# plug-v23-change-C-at-power-supply.net
KiCad netlist of a schematic drawn in EAGLE
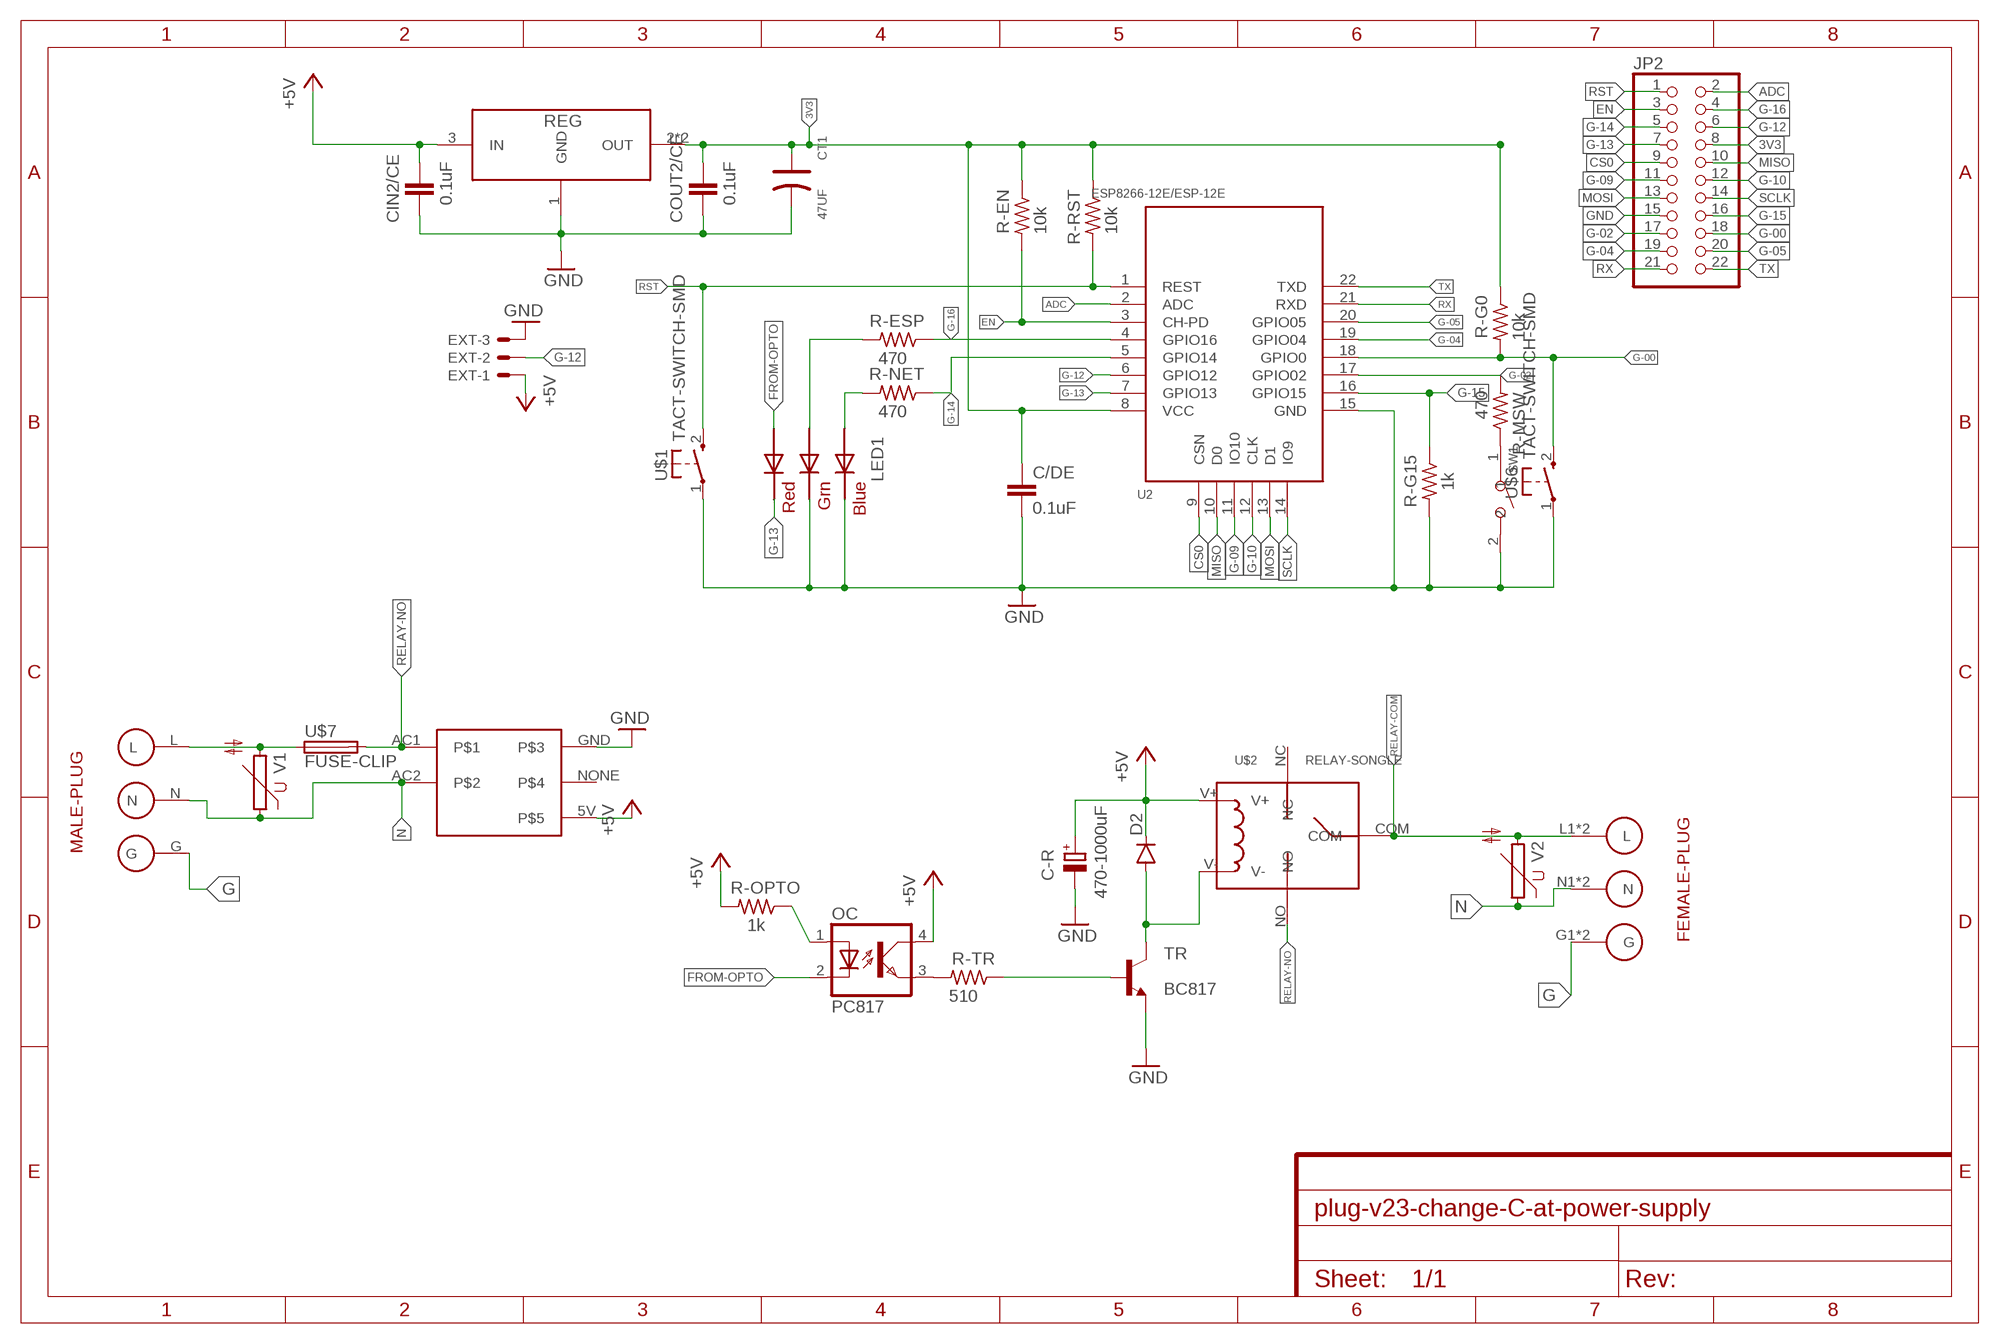
[diagram p0: schematic, sheet 1]

(export (version "E")
  (design (tool "Eeschema 10.0.6"))
  (components
    (comp (ref "C-R")
      (value "470-1000uF")
      (footprint "eagle-import:E3,5-8")
      (libsource (lib "eagle-import") (part "CPOL-EUE3.5-8"))
    )
    (comp (ref "C/DE")
      (value "0.1uF")
      (footprint "eagle-import:C0805")
      (libsource (lib "eagle-import") (part "C-EUC0805"))
    )
    (comp (ref "CIN2/CE")
      (value "0.1uF")
      (footprint "eagle-import:C0805K")
      (libsource (lib "eagle-import") (part "C-EUC0805K"))
    )
    (comp (ref "COUT2/CE")
      (value "0.1uF")
      (footprint "eagle-import:C0805K")
      (libsource (lib "eagle-import") (part "C-EUC0805K"))
    )
    (comp (ref "CT1")
      (value "47UF")
      (footprint "eagle-import:ELECTRO-SMD-C-6MM")
      (fields (field (name "MPN") "CS1E470M-CRE54"))
      (libsource (lib "eagle-import") (part "ALUMINUM-SMD-47UF-25V(D6.3-H5.3MM)"))
    )
    (comp (ref "D2")
      (value "DIODESOD123")
      (footprint "eagle-import:SOD-123")
      (libsource (lib "eagle-import") (part "DIODESOD123"))
    )
    (comp (ref "EXT")
      (value "53048-03")
      (footprint "eagle-import:53048-03")
      (fields (field (name "MF") "WALDOM/MOLEX") (field (name "MPN") "53048-0310"))
      (libsource (lib "eagle-import") (part "53?-03048"))
    )
    (comp (ref "JP2")
      (value "PINHD-2X11")
      (footprint "eagle-import:2X11")
      (libsource (lib "eagle-import") (part "PINHD-2X11"))
    )
    (comp (ref "LED1")
      (value "RGBLED5050")
      (footprint "eagle-import:RGBLED5050")
      (libsource (lib "eagle-import") (part "RGBLED5050"))
    )
    (comp (ref "OC")
      (value "PC817")
      (footprint "eagle-import:DIL04")
      (fields (field (name "MPN") "PC817X4J000F"))
      (libsource (lib "eagle-import") (part "PC817"))
    )
    (comp (ref "R-EN")
      (value "10k")
      (footprint "eagle-import:M0805")
      (libsource (lib "eagle-import") (part "R-US_M0805"))
    )
    (comp (ref "R-ESP")
      (value "470")
      (footprint "eagle-import:M0805")
      (libsource (lib "eagle-import") (part "R-US_M0805"))
    )
    (comp (ref "R-G0")
      (value "10k")
      (footprint "eagle-import:M0805")
      (libsource (lib "eagle-import") (part "R-US_M0805"))
    )
    (comp (ref "R-G15")
      (value "1k")
      (footprint "eagle-import:M0805")
      (libsource (lib "eagle-import") (part "R-US_M0805"))
    )
    (comp (ref "R-MSW")
      (value "470")
      (footprint "eagle-import:M0805")
      (libsource (lib "eagle-import") (part "R-US_M0805"))
    )
    (comp (ref "R-NET")
      (value "470")
      (footprint "eagle-import:M0805")
      (libsource (lib "eagle-import") (part "R-US_M0805"))
    )
    (comp (ref "R-OPTO")
      (value "1k")
      (footprint "eagle-import:M0805")
      (libsource (lib "eagle-import") (part "R-US_M0805"))
    )
    (comp (ref "R-RST")
      (value "10k")
      (footprint "eagle-import:M0805")
      (libsource (lib "eagle-import") (part "R-US_M0805"))
    )
    (comp (ref "R-TR")
      (value "510")
      (footprint "eagle-import:M0805")
      (libsource (lib "eagle-import") (part "R-US_M0805"))
    )
    (comp (ref "REG")
      (value "AMS1117-3.3")
      (footprint "eagle-import:SOT-223")
      (libsource (lib "eagle-import") (part "AMS1117-3.3"))
    )
    (comp (ref "SW1")
      (value "DIP-BUTTON(2P-6.0X3.0X4.3MM)-TS-1101F")
      (footprint "eagle-import:SW2-5.0-6.0X3.0X4.3MM")
      (libsource (lib "eagle-import") (part "DIP-BUTTON(2P-6.0X3.0X4.3MM)-TS-1101F"))
    )
    (comp (ref "TR")
      (value "BC817")
      (footprint "eagle-import:SOT23-BEC")
      (libsource (lib "eagle-import") (part "BC817SMD-16"))
    )
    (comp (ref "U$1")
      (value "TACT-SWITCH-SMD")
      (footprint "eagle-import:TACT-SWITCH-SMD")
      (libsource (lib "eagle-import") (part "TACT-SWITCH-SMD"))
    )
    (comp (ref "U$2")
      (value "RELAY-SONGLE")
      (footprint "eagle-import:RELAY-SONGLE")
      (libsource (lib "eagle-import") (part "RELAY-SONGLE"))
    )
    (comp (ref "U$3")
      (value "MALE-PLUG")
      (footprint "eagle-import:MALE-PLUG")
      (libsource (lib "eagle-import") (part "MALE-PLUG"))
    )
    (comp (ref "U$4")
      (value "POWERSUPPLY-5V-700MA")
      (footprint "eagle-import:POWERSUPPLY-5V-700MA")
      (libsource (lib "eagle-import") (part "POWERSUPPLY-5V-700MA"))
    )
    (comp (ref "U$5")
      (value "FEMALE-PLUG")
      (footprint "eagle-import:FEMALE-PLUG")
      (libsource (lib "eagle-import") (part "FEMALE-PLUG"))
    )
    (comp (ref "U$6")
      (value "TACT-SWITCH-SMD")
      (footprint "eagle-import:TACT-SWITCH-SMD")
      (libsource (lib "eagle-import") (part "TACT-SWITCH-SMD"))
    )
    (comp (ref "U$7")
      (value "FUSE-CLIP")
      (footprint "eagle-import:FUSE-CLIP")
      (libsource (lib "eagle-import") (part "FUSE-CLIP"))
    )
    (comp (ref "U2")
      (value "ESP8266-12E/ESP-12E")
      (footprint "eagle-import:LGA22-2.0-24X16MM")
      (libsource (lib "eagle-import") (part "MOUDLE-WIFI-ESP8266-12E/ESP-12E(22P-24X16MM)"))
    )
    (comp (ref "V1")
      (value "S14K11")
      (footprint "eagle-import:S14K11")
      (libsource (lib "eagle-import") (part "S14K11"))
    )
    (comp (ref "V2")
      (value "S14K11")
      (footprint "eagle-import:S14K11")
      (libsource (lib "eagle-import") (part "S14K11"))
    )
  )
  (nets
    (net (code "1") (name "+5V") (class "Default")
      (node (ref "C-R") (pin "+") (pinfunction "+_+") (pintype "passive"))
      (node (ref "CIN2/CE") (pin "1") (pinfunction "1_1") (pintype "passive"))
      (node (ref "D2") (pin "C") (pinfunction "C_C") (pintype "passive"))
      (node (ref "EXT") (pin "1") (pinfunction "S_1") (pintype "passive"))
      (node (ref "OC") (pin "4") (pinfunction "COL_4") (pintype "passive"))
      (node (ref "R-OPTO") (pin "2") (pinfunction "2_2") (pintype "passive"))
      (node (ref "REG") (pin "3") (pinfunction "IN_3") (pintype "input"))
      (node (ref "U$2") (pin "V+") (pinfunction "V+_V+") (pintype "bidirectional"))
      (node (ref "U$4") (pin "5V") (pinfunction "P$5_5V") (pintype "bidirectional"))
    )
    (net (code "2") (name "3V3") (class "Default")
      (node (ref "C/DE") (pin "1") (pinfunction "1_1") (pintype "passive"))
      (node (ref "COUT2/CE") (pin "1") (pinfunction "1_1") (pintype "passive"))
      (node (ref "CT1") (pin "+") (pinfunction "+_+") (pintype "passive"))
      (node (ref "JP2") (pin "8") (pinfunction "8_8") (pintype "passive"))
      (node (ref "R-EN") (pin "1") (pinfunction "1_1") (pintype "passive"))
      (node (ref "R-G0") (pin "1") (pinfunction "1_1") (pintype "passive"))
      (node (ref "R-RST") (pin "1") (pinfunction "1_1") (pintype "passive"))
      (node (ref "REG") (pin "2") (pinfunction "OUT_2") (pintype "output"))
      (node (ref "REG") (pin "4") (pinfunction "OUT_4") (pintype "output"))
      (node (ref "U2") (pin "8") (pinfunction "VCC_8") (pintype "bidirectional"))
    )
    (net (code "3") (name "ADC") (class "Default")
      (node (ref "JP2") (pin "2") (pinfunction "2_2") (pintype "passive"))
      (node (ref "U2") (pin "2") (pinfunction "ADC_2") (pintype "bidirectional"))
    )
    (net (code "4") (name "CS0") (class "Default")
      (node (ref "JP2") (pin "9") (pinfunction "9_9") (pintype "passive"))
      (node (ref "U2") (pin "9") (pinfunction "CSN_9") (pintype "bidirectional"))
    )
    (net (code "5") (name "EN") (class "Default")
      (node (ref "JP2") (pin "3") (pinfunction "3_3") (pintype "passive"))
      (node (ref "R-EN") (pin "2") (pinfunction "2_2") (pintype "passive"))
      (node (ref "U2") (pin "3") (pinfunction "CH-PD_3") (pintype "bidirectional"))
    )
    (net (code "6") (name "FROM-OPTO") (class "Default")
      (node (ref "LED1") (pin "2") (pinfunction "RED_A_2") (pintype "bidirectional"))
      (node (ref "OC") (pin "2") (pinfunction "C_2") (pintype "passive"))
    )
    (net (code "7") (name "G") (class "Default")
      (node (ref "U$3") (pin "G") (pinfunction "G_G") (pintype "bidirectional"))
      (node (ref "U$5") (pin "G1") (pinfunction "G_G1") (pintype "bidirectional"))
      (node (ref "U$5") (pin "G2") (pinfunction "G_G2") (pintype "bidirectional"))
    )
    (net (code "8") (name "G-00") (class "Default")
      (node (ref "JP2") (pin "18") (pinfunction "18_18") (pintype "passive"))
      (node (ref "R-G0") (pin "2") (pinfunction "2_2") (pintype "passive"))
      (node (ref "U$6") (pin "2") (pinfunction "S_2") (pintype "passive"))
      (node (ref "U2") (pin "18") (pinfunction "GPIO0_18") (pintype "bidirectional"))
    )
    (net (code "9") (name "G-02") (class "Default")
      (node (ref "JP2") (pin "17") (pinfunction "17_17") (pintype "passive"))
      (node (ref "R-MSW") (pin "2") (pinfunction "2_2") (pintype "passive"))
      (node (ref "U2") (pin "17") (pinfunction "GPIO02_17") (pintype "bidirectional"))
    )
    (net (code "10") (name "G-04") (class "Default")
      (node (ref "JP2") (pin "19") (pinfunction "19_19") (pintype "passive"))
      (node (ref "U2") (pin "19") (pinfunction "GPIO04_19") (pintype "bidirectional"))
    )
    (net (code "11") (name "G-05") (class "Default")
      (node (ref "JP2") (pin "20") (pinfunction "20_20") (pintype "passive"))
      (node (ref "U2") (pin "20") (pinfunction "GPIO05_20") (pintype "bidirectional"))
    )
    (net (code "12") (name "G-09") (class "Default")
      (node (ref "JP2") (pin "11") (pinfunction "11_11") (pintype "passive"))
      (node (ref "U2") (pin "11") (pinfunction "IO10_11") (pintype "bidirectional"))
    )
    (net (code "13") (name "G-10") (class "Default")
      (node (ref "JP2") (pin "12") (pinfunction "12_12") (pintype "passive"))
      (node (ref "U2") (pin "12") (pinfunction "CLK_12") (pintype "bidirectional"))
    )
    (net (code "14") (name "G-12") (class "Default")
      (node (ref "EXT") (pin "2") (pinfunction "S_2") (pintype "passive"))
      (node (ref "JP2") (pin "6") (pinfunction "6_6") (pintype "passive"))
      (node (ref "U2") (pin "6") (pinfunction "GPIO12_6") (pintype "bidirectional"))
    )
    (net (code "15") (name "G-13") (class "Default")
      (node (ref "JP2") (pin "7") (pinfunction "7_7") (pintype "passive"))
      (node (ref "LED1") (pin "5") (pinfunction "RED_C_5") (pintype "bidirectional"))
      (node (ref "U2") (pin "7") (pinfunction "GPIO13_7") (pintype "bidirectional"))
    )
    (net (code "16") (name "G-14") (class "Default")
      (node (ref "JP2") (pin "5") (pinfunction "5_5") (pintype "passive"))
      (node (ref "R-NET") (pin "1") (pinfunction "1_1") (pintype "passive"))
      (node (ref "U2") (pin "5") (pinfunction "GPIO14_5") (pintype "bidirectional"))
    )
    (net (code "17") (name "G-15") (class "Default")
      (node (ref "JP2") (pin "16") (pinfunction "16_16") (pintype "passive"))
      (node (ref "R-G15") (pin "1") (pinfunction "1_1") (pintype "passive"))
      (node (ref "U2") (pin "16") (pinfunction "GPIO15_16") (pintype "bidirectional"))
    )
    (net (code "18") (name "G-16") (class "Default")
      (node (ref "JP2") (pin "4") (pinfunction "4_4") (pintype "passive"))
      (node (ref "R-ESP") (pin "1") (pinfunction "1_1") (pintype "passive"))
      (node (ref "U2") (pin "4") (pinfunction "GPIO16_4") (pintype "bidirectional"))
    )
    (net (code "19") (name "GND") (class "Default")
      (node (ref "C-R") (pin "-") (pinfunction "-_-") (pintype "passive"))
      (node (ref "C/DE") (pin "2") (pinfunction "2_2") (pintype "passive"))
      (node (ref "CIN2/CE") (pin "2") (pinfunction "2_2") (pintype "passive"))
      (node (ref "COUT2/CE") (pin "2") (pinfunction "2_2") (pintype "passive"))
      (node (ref "CT1") (pin "-") (pinfunction "-_-") (pintype "passive"))
      (node (ref "EXT") (pin "3") (pinfunction "S_3") (pintype "passive"))
      (node (ref "JP2") (pin "15") (pinfunction "15_15") (pintype "passive"))
      (node (ref "LED1") (pin "4") (pinfunction "BLUE_C_4") (pintype "bidirectional"))
      (node (ref "LED1") (pin "6") (pinfunction "GREEN_C_6") (pintype "bidirectional"))
      (node (ref "R-G15") (pin "2") (pinfunction "2_2") (pintype "passive"))
      (node (ref "REG") (pin "1") (pinfunction "GND_1") (pintype "passive"))
      (node (ref "SW1") (pin "2") (pinfunction "2_2") (pintype "bidirectional"))
      (node (ref "TR") (pin "E") (pinfunction "E_E") (pintype "passive"))
      (node (ref "U$1") (pin "1") (pinfunction "P_1") (pintype "passive"))
      (node (ref "U$4") (pin "GND") (pinfunction "P$3_GND") (pintype "bidirectional"))
      (node (ref "U$6") (pin "1") (pinfunction "P_1") (pintype "passive"))
      (node (ref "U2") (pin "15") (pinfunction "GND_15") (pintype "bidirectional"))
    )
    (net (code "20") (name "MISO") (class "Default")
      (node (ref "JP2") (pin "10") (pinfunction "10_10") (pintype "passive"))
      (node (ref "U2") (pin "10") (pinfunction "D0_10") (pintype "bidirectional"))
    )
    (net (code "21") (name "MOSI") (class "Default")
      (node (ref "JP2") (pin "13") (pinfunction "13_13") (pintype "passive"))
      (node (ref "U2") (pin "13") (pinfunction "D1_13") (pintype "bidirectional"))
    )
    (net (code "22") (name "N") (class "Default")
      (node (ref "U$3") (pin "N") (pinfunction "N_N") (pintype "bidirectional"))
      (node (ref "U$4") (pin "AC2") (pinfunction "P$2_AC2") (pintype "bidirectional"))
      (node (ref "U$5") (pin "N1") (pinfunction "N_N1") (pintype "bidirectional"))
      (node (ref "U$5") (pin "N2") (pinfunction "N_N2") (pintype "bidirectional"))
      (node (ref "V1") (pin "1") (pinfunction "1_1") (pintype "passive"))
      (node (ref "V2") (pin "1") (pinfunction "1_1") (pintype "passive"))
    )
    (net (code "23") (name "Net-(D2-PadA)") (class "Default")
      (node (ref "D2") (pin "A") (pinfunction "A_A") (pintype "passive"))
      (node (ref "TR") (pin "C") (pinfunction "C_C") (pintype "passive"))
      (node (ref "U$2") (pin "V-") (pinfunction "V-_V-") (pintype "bidirectional"))
    )
    (net (code "24") (name "Net-(LED1-BLUE_A)") (class "Default")
      (node (ref "LED1") (pin "3") (pinfunction "BLUE_A_3") (pintype "bidirectional"))
      (node (ref "R-NET") (pin "2") (pinfunction "2_2") (pintype "passive"))
    )
    (net (code "25") (name "Net-(LED1-GREEN_A)") (class "Default")
      (node (ref "LED1") (pin "1") (pinfunction "GREEN_A_1") (pintype "bidirectional"))
      (node (ref "R-ESP") (pin "2") (pinfunction "2_2") (pintype "passive"))
    )
    (net (code "26") (name "Net-(OC-A)") (class "Default")
      (node (ref "OC") (pin "1") (pinfunction "A_1") (pintype "passive"))
      (node (ref "R-OPTO") (pin "1") (pinfunction "1_1") (pintype "passive"))
    )
    (net (code "27") (name "Net-(OC-EMIT)") (class "Default")
      (node (ref "OC") (pin "3") (pinfunction "EMIT_3") (pintype "passive"))
      (node (ref "R-TR") (pin "2") (pinfunction "2_2") (pintype "passive"))
    )
    (net (code "28") (name "Net-(R-MSW-Pad1)") (class "Default")
      (node (ref "R-MSW") (pin "1") (pinfunction "1_1") (pintype "passive"))
      (node (ref "SW1") (pin "1") (pinfunction "1_1") (pintype "bidirectional"))
    )
    (net (code "29") (name "Net-(R-TR-Pad1)") (class "Default")
      (node (ref "R-TR") (pin "1") (pinfunction "1_1") (pintype "passive"))
      (node (ref "TR") (pin "B") (pinfunction "B_B") (pintype "passive"))
    )
    (net (code "30") (name "Net-(U$3-PadL)") (class "Default")
      (node (ref "U$3") (pin "L") (pinfunction "L_L") (pintype "bidirectional"))
      (node (ref "U$7") (pin "3") (pinfunction "1_3") (pintype "passive"))
      (node (ref "U$7") (pin "4") (pinfunction "1_4") (pintype "passive"))
      (node (ref "V1") (pin "2") (pinfunction "2_2") (pintype "passive"))
    )
    (net (code "31") (name "RELAY-COM") (class "Default")
      (node (ref "U$2") (pin "COM") (pinfunction "COM_COM") (pintype "bidirectional"))
      (node (ref "U$5") (pin "L1") (pinfunction "L_L1") (pintype "bidirectional"))
      (node (ref "U$5") (pin "L2") (pinfunction "L_L2") (pintype "bidirectional"))
      (node (ref "V2") (pin "2") (pinfunction "2_2") (pintype "passive"))
    )
    (net (code "32") (name "RELAY-NO") (class "Default")
      (node (ref "U$2") (pin "NO") (pinfunction "NO_NO") (pintype "bidirectional"))
      (node (ref "U$4") (pin "AC1") (pinfunction "P$1_AC1") (pintype "bidirectional"))
      (node (ref "U$7") (pin "5") (pinfunction "2_5") (pintype "passive"))
      (node (ref "U$7") (pin "6") (pinfunction "2_6") (pintype "passive"))
    )
    (net (code "33") (name "RST") (class "Default")
      (node (ref "JP2") (pin "1") (pinfunction "1_1") (pintype "passive"))
      (node (ref "R-RST") (pin "2") (pinfunction "2_2") (pintype "passive"))
      (node (ref "U$1") (pin "2") (pinfunction "S_2") (pintype "passive"))
      (node (ref "U2") (pin "1") (pinfunction "REST_1") (pintype "bidirectional"))
    )
    (net (code "34") (name "RX") (class "Default")
      (node (ref "JP2") (pin "21") (pinfunction "21_21") (pintype "passive"))
      (node (ref "U2") (pin "21") (pinfunction "RXD_21") (pintype "bidirectional"))
    )
    (net (code "35") (name "SCLK") (class "Default")
      (node (ref "JP2") (pin "14") (pinfunction "14_14") (pintype "passive"))
      (node (ref "U2") (pin "14") (pinfunction "IO9_14") (pintype "bidirectional"))
    )
    (net (code "36") (name "TX") (class "Default")
      (node (ref "JP2") (pin "22") (pinfunction "22_22") (pintype "passive"))
      (node (ref "U2") (pin "22") (pinfunction "TXD_22") (pintype "bidirectional"))
    )
    (net (code "37") (name "unconnected-(U$2-PadNC)") (class "Default")
      (node (ref "U$2") (pin "NC") (pinfunction "NC_NC") (pintype "bidirectional"))
    )
    (net (code "38") (name "unconnected-(U$4-P$4-PadNONE)") (class "Default")
      (node (ref "U$4") (pin "NONE") (pinfunction "P$4_NONE") (pintype "bidirectional"))
    )
  )
)
